# CtrlCarbinBoard_Processor.net
KiCad netlist of a schematic drawn in Altium Designer
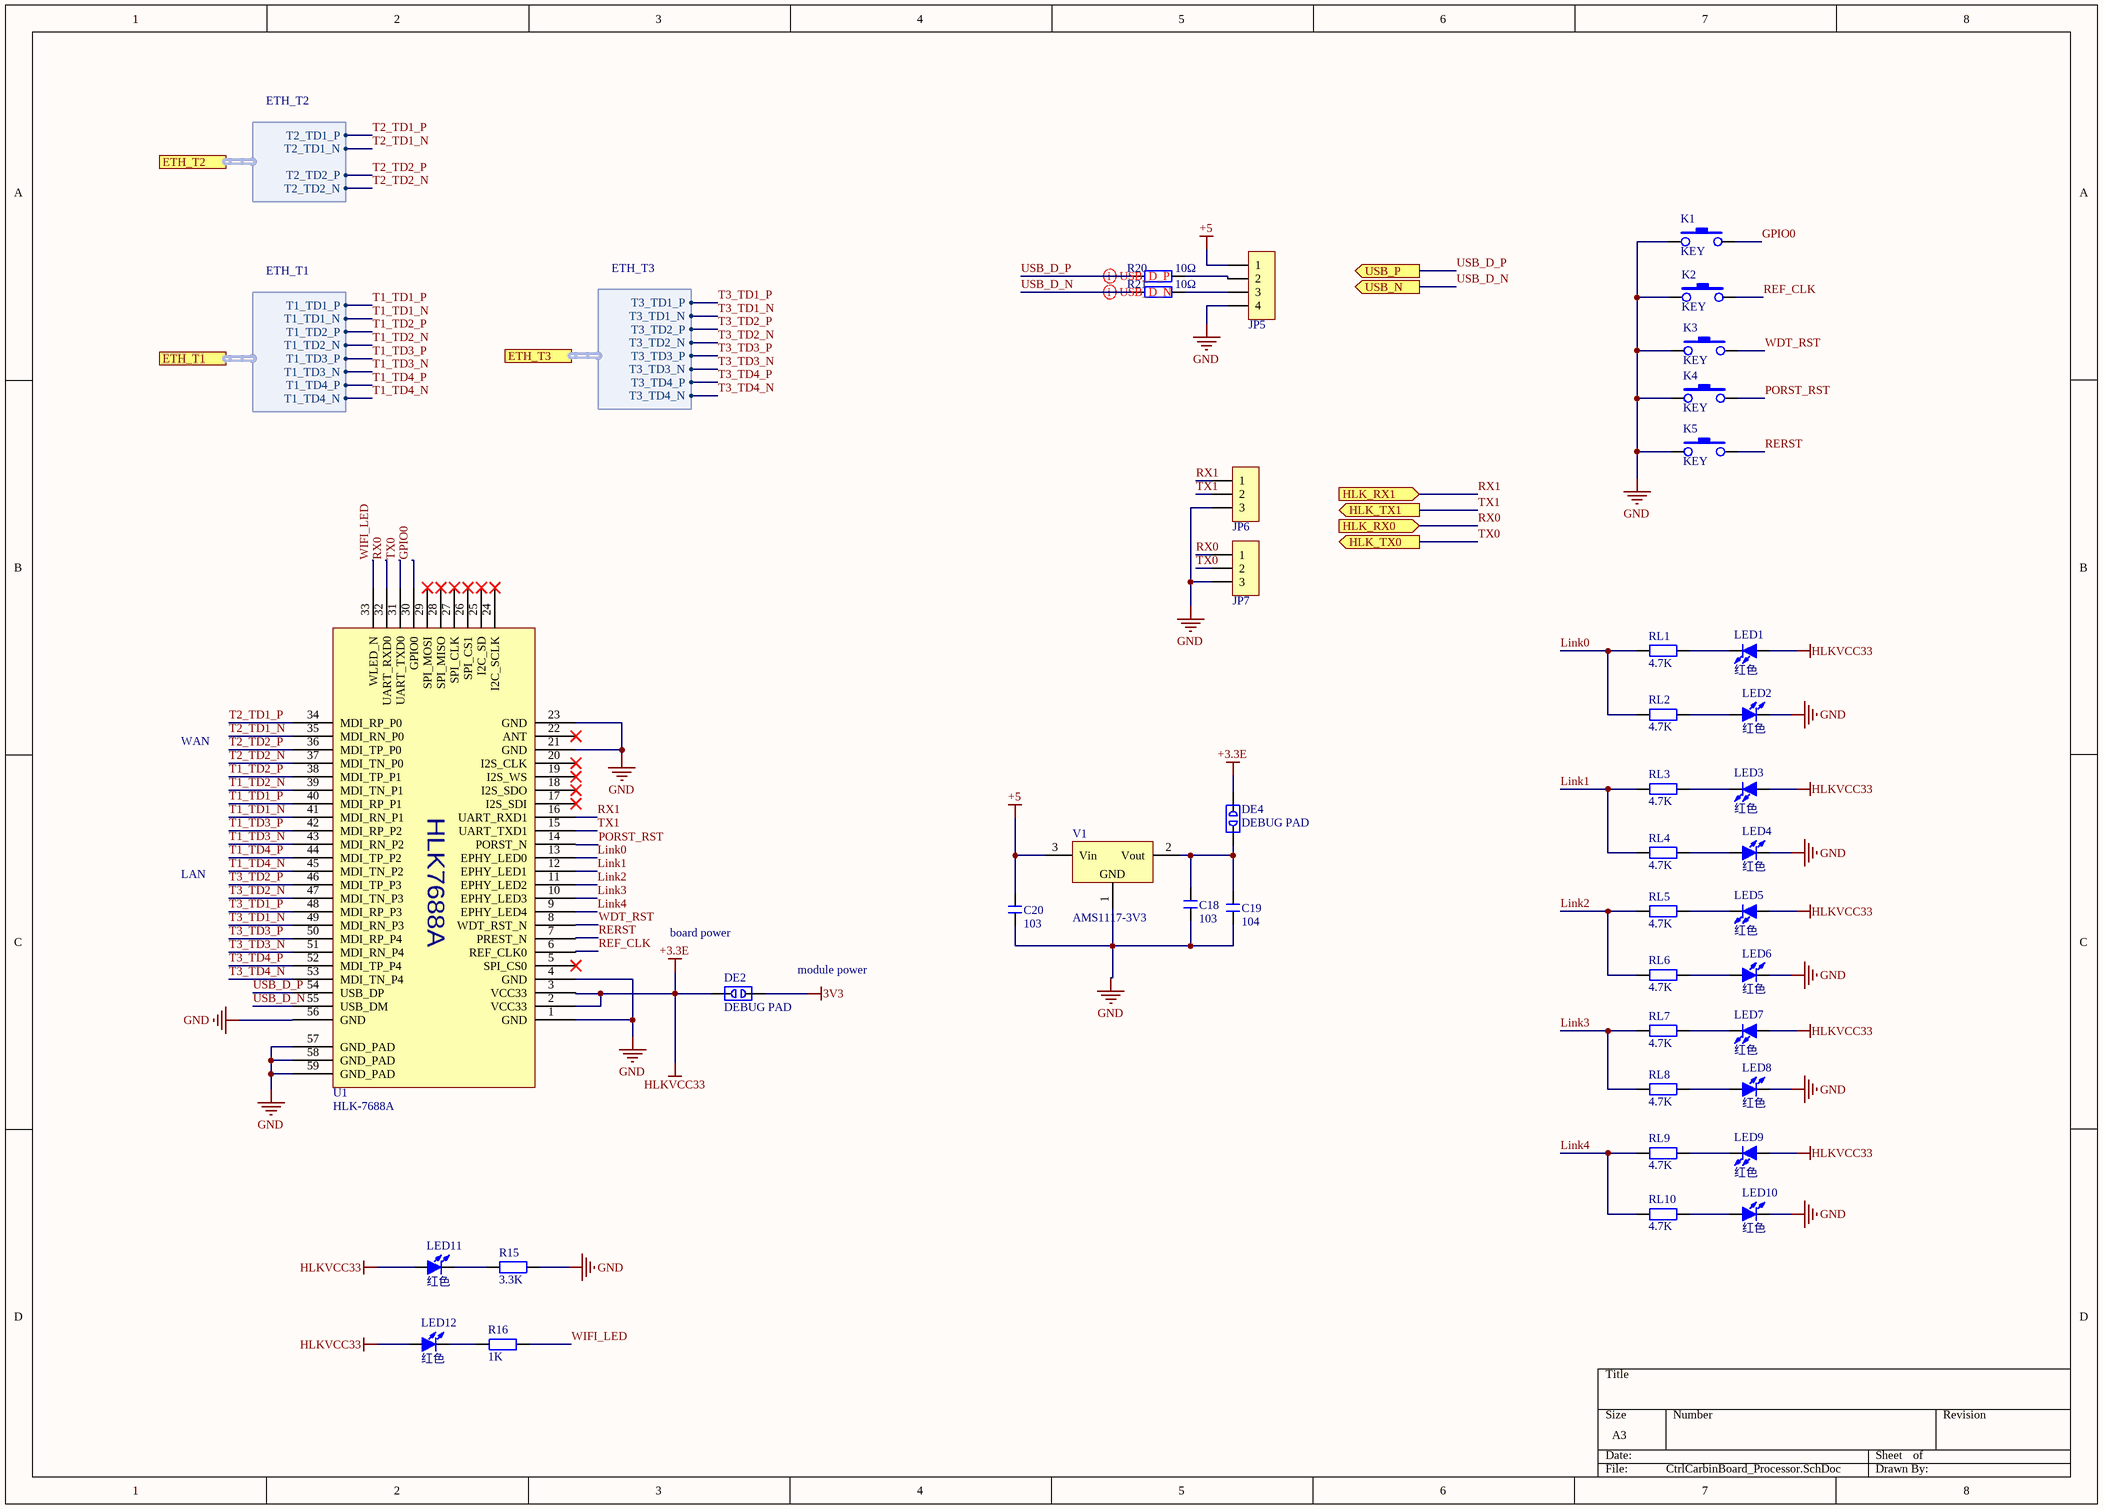
[diagram p0: CtrlCarbinBoard_Processor.SchDoc]

(export (version "E")
  (design (tool "Eeschema 10.0.6"))
  (components
    (comp (ref "C18")
      (value "103")
      (footprint "C 0603_L")
      (description "无极性贴片电容")
      (fields (field (name "版权归属") "源创客"))
      (libsource (lib "3.1   - 电阻-电容-电感") (part "C"))
    )
    (comp (ref "C19")
      (value "104")
      (footprint "C 0603_L")
      (description "无极性贴片电容")
      (fields (field (name "版权归属") "源创客"))
      (libsource (lib "3.1   - 电阻-电容-电感") (part "C"))
    )
    (comp (ref "C20")
      (value "103")
      (footprint "C 0603_L")
      (description "无极性贴片电容")
      (fields (field (name "版权归属") "源创客"))
      (libsource (lib "3.1   - 电阻-电容-电感") (part "C"))
    )
    (comp (ref "DE2")
      (value "DEBUG PAD")
      (footprint "DEBUG_B")
      (description "调试断点焊盘")
      (fields (field (name "版权归属") "源创客"))
      (libsource (lib "") (part "DEBUG_1"))
    )
    (comp (ref "DE4")
      (value "DEBUG PAD")
      (footprint "DEBUG_B")
      (description "调试断点焊盘")
      (fields (field (name "版权归属") "源创客"))
      (libsource (lib "15.1 - 未分类器件") (part "DEBUG"))
    )
    (comp (ref "JP5")
      (value "HDR-1X4")
      (footprint "HDR2.54-LI-4P")
      (description "4P接插件")
      (fields (field (name "版权归属") "源创客"))
      (libsource (lib "4.5   - 接插件-脚距2.54") (part "Header 4"))
    )
    (comp (ref "JP6")
      (value "HDR-1X3")
      (footprint "PH2.0-LS-3P")
      (description "3P接插件")
      (fields (field (name "版权归属") "源创客"))
      (libsource (lib "4.4   - 接插件-脚距2.0") (part "Header 3"))
    )
    (comp (ref "JP7")
      (value "HDR-1X3")
      (footprint "PH2.0-LS-3P")
      (description "3P接插件")
      (fields (field (name "版权归属") "源创客"))
      (libsource (lib "4.4   - 接插件-脚距2.0") (part "Header 3"))
    )
    (comp (ref "K1") (value "KEY") (footprint "SMD-3X6X2.5") (libsource (lib "轻触开关") (part "KEY")))
    (comp (ref "K2") (value "KEY") (footprint "SMD-3X6X2.5") (libsource (lib "轻触开关") (part "KEY")))
    (comp (ref "K3") (value "KEY") (footprint "SMD-3X6X2.5") (libsource (lib "轻触开关") (part "KEY")))
    (comp (ref "K4") (value "KEY") (footprint "SMD-3X6X2.5") (libsource (lib "轻触开关") (part "KEY")))
    (comp (ref "K5") (value "KEY") (footprint "SMD-3X6X2.5") (libsource (lib "轻触开关") (part "KEY")))
    (comp (ref "LED1")
      (value "红色")
      (footprint "LED 0603R")
      (description "贴片LED")
      (fields (field (name "版权归属") "源创客"))
      (libsource (lib "9.1   - LED") (part "LED-SMD"))
    )
    (comp (ref "LED2")
      (value "红色")
      (footprint "LED 0603R")
      (description "贴片LED")
      (fields (field (name "版权归属") "源创客"))
      (libsource (lib "9.1   - LED") (part "LED-SMD"))
    )
    (comp (ref "LED3")
      (value "红色")
      (footprint "LED 0603R")
      (description "贴片LED")
      (fields (field (name "版权归属") "源创客"))
      (libsource (lib "9.1   - LED") (part "LED-SMD"))
    )
    (comp (ref "LED4")
      (value "红色")
      (footprint "LED 0603R")
      (description "贴片LED")
      (fields (field (name "版权归属") "源创客"))
      (libsource (lib "9.1   - LED") (part "LED-SMD"))
    )
    (comp (ref "LED5")
      (value "红色")
      (footprint "LED 0603R")
      (description "贴片LED")
      (fields (field (name "版权归属") "源创客"))
      (libsource (lib "9.1   - LED") (part "LED-SMD"))
    )
    (comp (ref "LED6")
      (value "红色")
      (footprint "LED 0603R")
      (description "贴片LED")
      (fields (field (name "版权归属") "源创客"))
      (libsource (lib "9.1   - LED") (part "LED-SMD"))
    )
    (comp (ref "LED7")
      (value "红色")
      (footprint "LED 0603R")
      (description "贴片LED")
      (fields (field (name "版权归属") "源创客"))
      (libsource (lib "9.1   - LED") (part "LED-SMD"))
    )
    (comp (ref "LED8")
      (value "红色")
      (footprint "LED 0603R")
      (description "贴片LED")
      (fields (field (name "版权归属") "源创客"))
      (libsource (lib "9.1   - LED") (part "LED-SMD"))
    )
    (comp (ref "LED9")
      (value "红色")
      (footprint "LED 0603R")
      (description "贴片LED")
      (fields (field (name "版权归属") "源创客"))
      (libsource (lib "9.1   - LED") (part "LED-SMD"))
    )
    (comp (ref "LED10")
      (value "红色")
      (footprint "LED 0603R")
      (description "贴片LED")
      (fields (field (name "版权归属") "源创客"))
      (libsource (lib "9.1   - LED") (part "LED-SMD"))
    )
    (comp (ref "LED11")
      (value "红色")
      (footprint "LED 0805G")
      (description "贴片LED")
      (fields (field (name "版权归属") "源创客"))
      (libsource (lib "9.1   - LED") (part "LED-SMD"))
    )
    (comp (ref "LED12")
      (value "红色")
      (footprint "LED 0805G")
      (description "贴片LED")
      (fields (field (name "版权归属") "源创客"))
      (libsource (lib "9.1   - LED") (part "LED-SMD"))
    )
    (comp (ref "R15")
      (value "3.3K")
      (footprint "R 0603_L")
      (description "贴片电阻")
      (fields (field (name "版权归属") "源创客"))
      (libsource (lib "3.1   - 电阻-电容-电感") (part "R"))
    )
    (comp (ref "R16")
      (value "1K")
      (footprint "R 0603_L")
      (description "贴片电阻")
      (fields (field (name "版权归属") "源创客"))
      (libsource (lib "3.1   - 电阻-电容-电感") (part "R"))
    )
    (comp (ref "R20")
      (value "10Ω")
      (footprint "R 0603_L")
      (description "贴片电阻")
      (fields (field (name "版权归属") "源创客"))
      (libsource (lib "3.1   - 电阻-电容-电感") (part "R"))
    )
    (comp (ref "R21")
      (value "10Ω")
      (footprint "R 0603_L")
      (description "贴片电阻")
      (fields (field (name "版权归属") "源创客"))
      (libsource (lib "3.1   - 电阻-电容-电感") (part "R"))
    )
    (comp (ref "RL1")
      (value "4.7K")
      (footprint "R 0603_L")
      (description "贴片电阻")
      (fields (field (name "版权归属") "源创客"))
      (libsource (lib "3.1   - 电阻-电容-电感") (part "R"))
    )
    (comp (ref "RL2")
      (value "4.7K")
      (footprint "R 0603_L")
      (description "贴片电阻")
      (fields (field (name "版权归属") "源创客"))
      (libsource (lib "3.1   - 电阻-电容-电感") (part "R"))
    )
    (comp (ref "RL3")
      (value "4.7K")
      (footprint "R 0603_L")
      (description "贴片电阻")
      (fields (field (name "版权归属") "源创客"))
      (libsource (lib "3.1   - 电阻-电容-电感") (part "R"))
    )
    (comp (ref "RL4")
      (value "4.7K")
      (footprint "R 0603_L")
      (description "贴片电阻")
      (fields (field (name "版权归属") "源创客"))
      (libsource (lib "3.1   - 电阻-电容-电感") (part "R"))
    )
    (comp (ref "RL5")
      (value "4.7K")
      (footprint "R 0603_L")
      (description "贴片电阻")
      (fields (field (name "版权归属") "源创客"))
      (libsource (lib "3.1   - 电阻-电容-电感") (part "R"))
    )
    (comp (ref "RL6")
      (value "4.7K")
      (footprint "R 0603_L")
      (description "贴片电阻")
      (fields (field (name "版权归属") "源创客"))
      (libsource (lib "3.1   - 电阻-电容-电感") (part "R"))
    )
    (comp (ref "RL7")
      (value "4.7K")
      (footprint "R 0603_L")
      (description "贴片电阻")
      (fields (field (name "版权归属") "源创客"))
      (libsource (lib "3.1   - 电阻-电容-电感") (part "R"))
    )
    (comp (ref "RL8")
      (value "4.7K")
      (footprint "R 0603_L")
      (description "贴片电阻")
      (fields (field (name "版权归属") "源创客"))
      (libsource (lib "3.1   - 电阻-电容-电感") (part "R"))
    )
    (comp (ref "RL9")
      (value "4.7K")
      (footprint "R 0603_L")
      (description "贴片电阻")
      (fields (field (name "版权归属") "源创客"))
      (libsource (lib "3.1   - 电阻-电容-电感") (part "R"))
    )
    (comp (ref "RL10")
      (value "4.7K")
      (footprint "R 0603_L")
      (description "贴片电阻")
      (fields (field (name "版权归属") "源创客"))
      (libsource (lib "3.1   - 电阻-电容-电感") (part "R"))
    )
    (comp (ref "U1") (value "HLK-7688A") (footprint "7688A") (libsource (lib "MySchLib") (part "HLK-7688A")))
    (comp (ref "V1")
      (value "AMS1117-3V3")
      (footprint "SOT223_M")
      (description "三端稳压芯片")
      (fields (field (name "版权归属") "源创客"))
      (libsource (lib "1.3   - 电源类芯片") (part "AMS1117"))
    )
  )
  (nets
    (net (code "4") (name "+3.3E") (class "Default")
      (node (ref "DE2") (pin "1") (pinfunction "1_1") (pintype "passive"))
      (node (ref "DE4") (pin "2") (pinfunction "2_2") (pintype "passive"))
      (node (ref "LED1") (pin "1") (pinfunction "A_1") (pintype "passive"))
      (node (ref "LED11") (pin "1") (pinfunction "A_1") (pintype "passive"))
      (node (ref "LED12") (pin "1") (pinfunction "A_1") (pintype "passive"))
      (node (ref "LED3") (pin "1") (pinfunction "A_1") (pintype "passive"))
      (node (ref "LED5") (pin "1") (pinfunction "A_1") (pintype "passive"))
      (node (ref "LED7") (pin "1") (pinfunction "A_1") (pintype "passive"))
      (node (ref "LED9") (pin "1") (pinfunction "A_1") (pintype "passive"))
      (node (ref "U1") (pin "2") (pinfunction "VCC33_2") (pintype "passive"))
      (node (ref "U1") (pin "3") (pinfunction "VCC33_3") (pintype "passive"))
    )
    (net (code "5") (name "+5") (class "Default")
      (node (ref "C20") (pin "2") (pinfunction "2_2") (pintype "passive"))
      (node (ref "JP5") (pin "1") (pinfunction "1_1") (pintype "passive"))
      (node (ref "V1") (pin "3") (pinfunction "Vin_3") (pintype "passive"))
    )
    (net (code "6") (name "/GPIO0") (class "Default")
      (node (ref "K1") (pin "3") (pinfunction "3_3") (pintype "passive"))
      (node (ref "U1") (pin "30") (pinfunction "GPIO0_30") (pintype "passive"))
    )
    (net (code "7") (name "/Link0") (class "Default")
      (node (ref "RL1") (pin "2") (pinfunction "2_2") (pintype "passive"))
      (node (ref "RL2") (pin "2") (pinfunction "2_2") (pintype "passive"))
      (node (ref "U1") (pin "13") (pinfunction "EPHY_LED0_13") (pintype "passive"))
    )
    (net (code "8") (name "/Link1") (class "Default")
      (node (ref "RL3") (pin "2") (pinfunction "2_2") (pintype "passive"))
      (node (ref "RL4") (pin "2") (pinfunction "2_2") (pintype "passive"))
      (node (ref "U1") (pin "12") (pinfunction "EPHY_LED1_12") (pintype "passive"))
    )
    (net (code "9") (name "/Link2") (class "Default")
      (node (ref "RL5") (pin "2") (pinfunction "2_2") (pintype "passive"))
      (node (ref "RL6") (pin "2") (pinfunction "2_2") (pintype "passive"))
      (node (ref "U1") (pin "11") (pinfunction "EPHY_LED2_11") (pintype "passive"))
    )
    (net (code "10") (name "/Link3") (class "Default")
      (node (ref "RL7") (pin "2") (pinfunction "2_2") (pintype "passive"))
      (node (ref "RL8") (pin "2") (pinfunction "2_2") (pintype "passive"))
      (node (ref "U1") (pin "10") (pinfunction "EPHY_LED3_10") (pintype "passive"))
    )
    (net (code "11") (name "/Link4") (class "Default")
      (node (ref "RL10") (pin "2") (pinfunction "2_2") (pintype "passive"))
      (node (ref "RL9") (pin "2") (pinfunction "2_2") (pintype "passive"))
      (node (ref "U1") (pin "9") (pinfunction "EPHY_LED4_9") (pintype "passive"))
    )
    (net (code "12") (name "/PORST_RST") (class "Default")
      (node (ref "K4") (pin "3") (pinfunction "3_3") (pintype "passive"))
      (node (ref "U1") (pin "14") (pinfunction "PORST_N_14") (pintype "passive"))
    )
    (net (code "13") (name "/REF_CLK") (class "Default")
      (node (ref "K2") (pin "3") (pinfunction "3_3") (pintype "passive"))
      (node (ref "U1") (pin "6") (pinfunction "REF_CLK0_6") (pintype "passive"))
    )
    (net (code "14") (name "/RERST") (class "Default")
      (node (ref "K5") (pin "3") (pinfunction "3_3") (pintype "passive"))
      (node (ref "U1") (pin "7") (pinfunction "PREST_N_7") (pintype "passive"))
    )
    (net (code "15") (name "/RX0") (class "Default")
      (node (ref "JP7") (pin "1") (pinfunction "1_1") (pintype "passive"))
      (node (ref "U1") (pin "32") (pinfunction "UART_RXD0_32") (pintype "passive"))
    )
    (net (code "16") (name "/RX1") (class "Default")
      (node (ref "JP6") (pin "1") (pinfunction "1_1") (pintype "passive"))
      (node (ref "U1") (pin "16") (pinfunction "UART_RXD1_16") (pintype "passive"))
    )
    (net (code "17") (name "/T1_TD1_N") (class "Default")
      (node (ref "U1") (pin "41") (pinfunction "MDI_RN_P1_41") (pintype "passive"))
    )
    (net (code "18") (name "/T1_TD1_P") (class "Default")
      (node (ref "U1") (pin "40") (pinfunction "MDI_RP_P1_40") (pintype "passive"))
    )
    (net (code "19") (name "/T1_TD2_N") (class "Default")
      (node (ref "U1") (pin "39") (pinfunction "MDI_TN_P1_39") (pintype "passive"))
    )
    (net (code "20") (name "/T1_TD2_P") (class "Default")
      (node (ref "U1") (pin "38") (pinfunction "MDI_TP_P1_38") (pintype "passive"))
    )
    (net (code "21") (name "/T1_TD3_N") (class "Default")
      (node (ref "U1") (pin "43") (pinfunction "MDI_RN_P2_43") (pintype "passive"))
    )
    (net (code "22") (name "/T1_TD3_P") (class "Default")
      (node (ref "U1") (pin "42") (pinfunction "MDI_RP_P2_42") (pintype "passive"))
    )
    (net (code "23") (name "/T1_TD4_N") (class "Default")
      (node (ref "U1") (pin "45") (pinfunction "MDI_TN_P2_45") (pintype "passive"))
    )
    (net (code "24") (name "/T1_TD4_P") (class "Default")
      (node (ref "U1") (pin "44") (pinfunction "MDI_TP_P2_44") (pintype "passive"))
    )
    (net (code "25") (name "/T2_TD1_N") (class "Default")
      (node (ref "U1") (pin "35") (pinfunction "MDI_RN_P0_35") (pintype "passive"))
    )
    (net (code "26") (name "/T2_TD1_P") (class "Default")
      (node (ref "U1") (pin "34") (pinfunction "MDI_RP_P0_34") (pintype "passive"))
    )
    (net (code "27") (name "/T2_TD2_N") (class "Default")
      (node (ref "U1") (pin "37") (pinfunction "MDI_TN_P0_37") (pintype "passive"))
    )
    (net (code "28") (name "/T2_TD2_P") (class "Default")
      (node (ref "U1") (pin "36") (pinfunction "MDI_TP_P0_36") (pintype "passive"))
    )
    (net (code "29") (name "/T3_TD1_N") (class "Default")
      (node (ref "U1") (pin "49") (pinfunction "MDI_RN_P3_49") (pintype "passive"))
    )
    (net (code "30") (name "/T3_TD1_P") (class "Default")
      (node (ref "U1") (pin "48") (pinfunction "MDI_RP_P3_48") (pintype "passive"))
    )
    (net (code "31") (name "/T3_TD2_N") (class "Default")
      (node (ref "U1") (pin "47") (pinfunction "MDI_TN_P3_47") (pintype "passive"))
    )
    (net (code "32") (name "/T3_TD2_P") (class "Default")
      (node (ref "U1") (pin "46") (pinfunction "MDI_TP_P3_46") (pintype "passive"))
    )
    (net (code "33") (name "/T3_TD3_N") (class "Default")
      (node (ref "U1") (pin "51") (pinfunction "MDI_RN_P4_51") (pintype "passive"))
    )
    (net (code "34") (name "/T3_TD3_P") (class "Default")
      (node (ref "U1") (pin "50") (pinfunction "MDI_RP_P4_50") (pintype "passive"))
    )
    (net (code "35") (name "/T3_TD4_N") (class "Default")
      (node (ref "U1") (pin "53") (pinfunction "MDI_TN_P4_53") (pintype "passive"))
    )
    (net (code "36") (name "/T3_TD4_P") (class "Default")
      (node (ref "U1") (pin "52") (pinfunction "MDI_TP_P4_52") (pintype "passive"))
    )
    (net (code "37") (name "/TX0") (class "Default")
      (node (ref "JP7") (pin "2") (pinfunction "2_2") (pintype "passive"))
      (node (ref "U1") (pin "31") (pinfunction "UART_TXD0_31") (pintype "passive"))
    )
    (net (code "38") (name "/TX1") (class "Default")
      (node (ref "JP6") (pin "2") (pinfunction "2_2") (pintype "passive"))
      (node (ref "U1") (pin "15") (pinfunction "UART_TXD1_15") (pintype "passive"))
    )
    (net (code "39") (name "/USB_D_N") (class "Default")
      (node (ref "R21") (pin "1") (pinfunction "1_1") (pintype "passive"))
      (node (ref "U1") (pin "55") (pinfunction "USB_DM_55") (pintype "passive"))
    )
    (net (code "40") (name "/USB_D_P") (class "Default")
      (node (ref "R20") (pin "1") (pinfunction "1_1") (pintype "passive"))
      (node (ref "U1") (pin "54") (pinfunction "USB_DP_54") (pintype "passive"))
    )
    (net (code "41") (name "/WDT_RST") (class "Default")
      (node (ref "K3") (pin "3") (pinfunction "3_3") (pintype "passive"))
      (node (ref "U1") (pin "8") (pinfunction "WDT_RST_N_8") (pintype "passive"))
    )
    (net (code "42") (name "/WIFI_LED") (class "Default")
      (node (ref "R16") (pin "2") (pinfunction "2_2") (pintype "passive"))
      (node (ref "U1") (pin "33") (pinfunction "WLED_N_33") (pintype "passive"))
    )
    (net (code "46") (name "3V3") (class "Default")
      (node (ref "DE2") (pin "2") (pinfunction "2_2") (pintype "passive"))
    )
    (net (code "47") (name "GND") (class "Default")
      (node (ref "C18") (pin "1") (pinfunction "1_1") (pintype "passive"))
      (node (ref "C19") (pin "1") (pinfunction "1_1") (pintype "passive"))
      (node (ref "C20") (pin "1") (pinfunction "1_1") (pintype "passive"))
      (node (ref "JP5") (pin "4") (pinfunction "4_4") (pintype "passive"))
      (node (ref "JP6") (pin "3") (pinfunction "3_3") (pintype "passive"))
      (node (ref "JP7") (pin "3") (pinfunction "3_3") (pintype "passive"))
      (node (ref "K1") (pin "1") (pinfunction "1_1") (pintype "passive"))
      (node (ref "K2") (pin "1") (pinfunction "1_1") (pintype "passive"))
      (node (ref "K3") (pin "1") (pinfunction "1_1") (pintype "passive"))
      (node (ref "K4") (pin "1") (pinfunction "1_1") (pintype "passive"))
      (node (ref "K5") (pin "1") (pinfunction "1_1") (pintype "passive"))
      (node (ref "LED10") (pin "2") (pinfunction "K_2") (pintype "passive"))
      (node (ref "LED2") (pin "2") (pinfunction "K_2") (pintype "passive"))
      (node (ref "LED4") (pin "2") (pinfunction "K_2") (pintype "passive"))
      (node (ref "LED6") (pin "2") (pinfunction "K_2") (pintype "passive"))
      (node (ref "LED8") (pin "2") (pinfunction "K_2") (pintype "passive"))
      (node (ref "R15") (pin "2") (pinfunction "2_2") (pintype "passive"))
      (node (ref "U1") (pin "1") (pinfunction "GND_1") (pintype "passive"))
      (node (ref "U1") (pin "21") (pinfunction "GND_21") (pintype "passive"))
      (node (ref "U1") (pin "23") (pinfunction "GND_23") (pintype "passive"))
      (node (ref "U1") (pin "4") (pinfunction "GND_4") (pintype "passive"))
      (node (ref "U1") (pin "56") (pinfunction "GND_56") (pintype "passive"))
      (node (ref "U1") (pin "57") (pinfunction "GND_PAD_57") (pintype "passive"))
      (node (ref "U1") (pin "58") (pinfunction "GND_PAD_58") (pintype "passive"))
      (node (ref "U1") (pin "59") (pinfunction "GND_PAD_59") (pintype "passive"))
      (node (ref "V1") (pin "1") (pinfunction "GND_1") (pintype "passive"))
    )
    (net (code "48") (name "Net-(JP5-Pad2)") (class "Default")
      (node (ref "JP5") (pin "2") (pinfunction "2_2") (pintype "passive"))
      (node (ref "R20") (pin "2") (pinfunction "2_2") (pintype "passive"))
    )
    (net (code "49") (name "Net-(JP5-Pad3)") (class "Default")
      (node (ref "JP5") (pin "3") (pinfunction "3_3") (pintype "passive"))
      (node (ref "R21") (pin "2") (pinfunction "2_2") (pintype "passive"))
    )
    (net (code "50") (name "Net-(LED1-K)") (class "Default")
      (node (ref "LED1") (pin "2") (pinfunction "K_2") (pintype "passive"))
      (node (ref "RL1") (pin "1") (pinfunction "1_1") (pintype "passive"))
    )
    (net (code "51") (name "Net-(LED2-A)") (class "Default")
      (node (ref "LED2") (pin "1") (pinfunction "A_1") (pintype "passive"))
      (node (ref "RL2") (pin "1") (pinfunction "1_1") (pintype "passive"))
    )
    (net (code "52") (name "Net-(LED3-K)") (class "Default")
      (node (ref "LED3") (pin "2") (pinfunction "K_2") (pintype "passive"))
      (node (ref "RL3") (pin "1") (pinfunction "1_1") (pintype "passive"))
    )
    (net (code "53") (name "Net-(LED4-A)") (class "Default")
      (node (ref "LED4") (pin "1") (pinfunction "A_1") (pintype "passive"))
      (node (ref "RL4") (pin "1") (pinfunction "1_1") (pintype "passive"))
    )
    (net (code "54") (name "Net-(LED5-K)") (class "Default")
      (node (ref "LED5") (pin "2") (pinfunction "K_2") (pintype "passive"))
      (node (ref "RL5") (pin "1") (pinfunction "1_1") (pintype "passive"))
    )
    (net (code "55") (name "Net-(LED6-A)") (class "Default")
      (node (ref "LED6") (pin "1") (pinfunction "A_1") (pintype "passive"))
      (node (ref "RL6") (pin "1") (pinfunction "1_1") (pintype "passive"))
    )
    (net (code "56") (name "Net-(LED7-K)") (class "Default")
      (node (ref "LED7") (pin "2") (pinfunction "K_2") (pintype "passive"))
      (node (ref "RL7") (pin "1") (pinfunction "1_1") (pintype "passive"))
    )
    (net (code "57") (name "Net-(LED8-A)") (class "Default")
      (node (ref "LED8") (pin "1") (pinfunction "A_1") (pintype "passive"))
      (node (ref "RL8") (pin "1") (pinfunction "1_1") (pintype "passive"))
    )
    (net (code "58") (name "Net-(LED9-K)") (class "Default")
      (node (ref "LED9") (pin "2") (pinfunction "K_2") (pintype "passive"))
      (node (ref "RL9") (pin "1") (pinfunction "1_1") (pintype "passive"))
    )
    (net (code "59") (name "Net-(LED10-A)") (class "Default")
      (node (ref "LED10") (pin "1") (pinfunction "A_1") (pintype "passive"))
      (node (ref "RL10") (pin "1") (pinfunction "1_1") (pintype "passive"))
    )
    (net (code "60") (name "Net-(LED11-K)") (class "Default")
      (node (ref "LED11") (pin "2") (pinfunction "K_2") (pintype "passive"))
      (node (ref "R15") (pin "1") (pinfunction "1_1") (pintype "passive"))
    )
    (net (code "61") (name "Net-(LED12-K)") (class "Default")
      (node (ref "LED12") (pin "2") (pinfunction "K_2") (pintype "passive"))
      (node (ref "R16") (pin "1") (pinfunction "1_1") (pintype "passive"))
    )
    (net (code "62") (name "Net-(V1-Vout)") (class "Default")
      (node (ref "C18") (pin "2") (pinfunction "2_2") (pintype "passive"))
      (node (ref "C19") (pin "2") (pinfunction "2_2") (pintype "passive"))
      (node (ref "DE4") (pin "1") (pinfunction "1_1") (pintype "passive"))
      (node (ref "V1") (pin "2") (pinfunction "Vout_2") (pintype "passive"))
    )
    (net (code "63") (name "unconnected-(U1-ANT-Pad22)") (class "Default")
      (node (ref "U1") (pin "22") (pinfunction "ANT_22") (pintype "passive+no_connect"))
    )
    (net (code "64") (name "unconnected-(U1-I2C_SCLK-Pad24)") (class "Default")
      (node (ref "U1") (pin "24") (pinfunction "I2C_SCLK_24") (pintype "passive+no_connect"))
    )
    (net (code "65") (name "unconnected-(U1-I2C_SD-Pad25)") (class "Default")
      (node (ref "U1") (pin "25") (pinfunction "I2C_SD_25") (pintype "passive+no_connect"))
    )
    (net (code "66") (name "unconnected-(U1-I2S_CLK-Pad20)") (class "Default")
      (node (ref "U1") (pin "20") (pinfunction "I2S_CLK_20") (pintype "passive+no_connect"))
    )
    (net (code "67") (name "unconnected-(U1-I2S_SDI-Pad17)") (class "Default")
      (node (ref "U1") (pin "17") (pinfunction "I2S_SDI_17") (pintype "passive+no_connect"))
    )
    (net (code "68") (name "unconnected-(U1-I2S_SDO-Pad18)") (class "Default")
      (node (ref "U1") (pin "18") (pinfunction "I2S_SDO_18") (pintype "passive+no_connect"))
    )
    (net (code "69") (name "unconnected-(U1-I2S_WS-Pad19)") (class "Default")
      (node (ref "U1") (pin "19") (pinfunction "I2S_WS_19") (pintype "passive+no_connect"))
    )
    (net (code "70") (name "unconnected-(U1-SPI_CLK-Pad27)") (class "Default")
      (node (ref "U1") (pin "27") (pinfunction "SPI_CLK_27") (pintype "passive+no_connect"))
    )
    (net (code "71") (name "unconnected-(U1-SPI_CS0-Pad5)") (class "Default")
      (node (ref "U1") (pin "5") (pinfunction "SPI_CS0_5") (pintype "passive+no_connect"))
    )
    (net (code "72") (name "unconnected-(U1-SPI_CS1-Pad26)") (class "Default")
      (node (ref "U1") (pin "26") (pinfunction "SPI_CS1_26") (pintype "passive+no_connect"))
    )
    (net (code "73") (name "unconnected-(U1-SPI_MISO-Pad28)") (class "Default")
      (node (ref "U1") (pin "28") (pinfunction "SPI_MISO_28") (pintype "passive+no_connect"))
    )
    (net (code "74") (name "unconnected-(U1-SPI_MOSI-Pad29)") (class "Default")
      (node (ref "U1") (pin "29") (pinfunction "SPI_MOSI_29") (pintype "passive+no_connect"))
    )
  )
)
